# LED-RGB.net
KiCad netlist of a schematic drawn in EAGLE
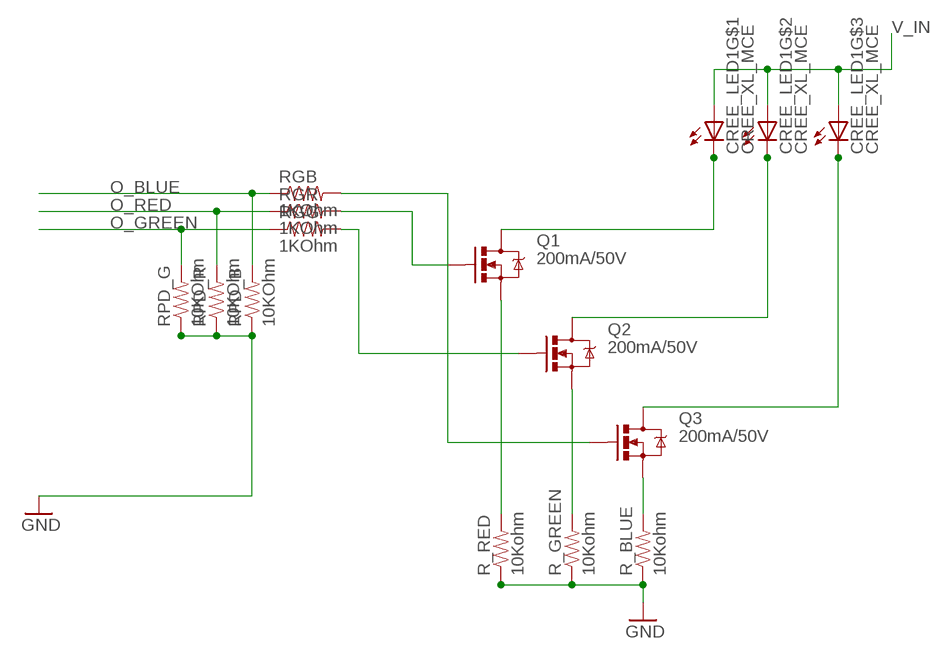
[diagram p0: schematic, sheet 1]

(export (version "E")
  (design (tool "Eeschema 10.0.6"))
  (components
    (comp (ref "CREE_LED1")
      (value "CREE_XL_MCE")
      (footprint "eagle-import:CREE_XL_MCE")
      (libsource (lib "eagle-import") (part "CREE_XL_MCE"))
    )
    (comp (ref "Q1")
      (value "200mA/50V")
      (footprint "eagle-import:SOT23-3")
      (libsource (lib "eagle-import") (part "MOSFET-NCHANNELBSS138"))
    )
    (comp (ref "Q2")
      (value "200mA/50V")
      (footprint "eagle-import:SOT23-3")
      (libsource (lib "eagle-import") (part "MOSFET-NCHANNELBSS138"))
    )
    (comp (ref "Q3")
      (value "200mA/50V")
      (footprint "eagle-import:SOT23-3")
      (libsource (lib "eagle-import") (part "MOSFET-NCHANNELBSS138"))
    )
    (comp (ref "RGB")
      (value "1KOhm")
      (footprint "eagle-import:0805")
      (libsource (lib "eagle-import") (part "RESISTOR0805-RES"))
    )
    (comp (ref "RGG")
      (value "1KOhm")
      (footprint "eagle-import:0805")
      (libsource (lib "eagle-import") (part "RESISTOR0805-RES"))
    )
    (comp (ref "RGR")
      (value "1KOhm")
      (footprint "eagle-import:0805")
      (libsource (lib "eagle-import") (part "RESISTOR0805-RES"))
    )
    (comp (ref "RPD_B")
      (value "10KOhm")
      (footprint "eagle-import:0805")
      (libsource (lib "eagle-import") (part "RESISTOR0805-RES"))
    )
    (comp (ref "RPD_G")
      (value "10KOhm")
      (footprint "eagle-import:0805")
      (libsource (lib "eagle-import") (part "RESISTOR0805-RES"))
    )
    (comp (ref "RPD_R")
      (value "10KOhm")
      (footprint "eagle-import:0805")
      (libsource (lib "eagle-import") (part "RESISTOR0805-RES"))
    )
    (comp (ref "R_BLUE")
      (value "10Kohm")
      (footprint "eagle-import:0805")
      (libsource (lib "eagle-import") (part "RESISTOR0805-RES"))
    )
    (comp (ref "R_GREEN")
      (value "10Kohm")
      (footprint "eagle-import:0805")
      (libsource (lib "eagle-import") (part "RESISTOR0805-RES"))
    )
    (comp (ref "R_RED")
      (value "10Kohm")
      (footprint "eagle-import:0805")
      (libsource (lib "eagle-import") (part "RESISTOR0805-RES"))
    )
  )
  (nets
    (net (code "1") (name "/O_BLUE") (class "Default")
      (node (ref "RGB") (pin "1") (pinfunction "1_1") (pintype "passive"))
      (node (ref "RPD_B") (pin "2") (pinfunction "2_2") (pintype "passive"))
    )
    (net (code "2") (name "/O_GREEN") (class "Default")
      (node (ref "RGG") (pin "1") (pinfunction "1_1") (pintype "passive"))
      (node (ref "RPD_G") (pin "2") (pinfunction "2_2") (pintype "passive"))
    )
    (net (code "3") (name "/O_RED") (class "Default")
      (node (ref "RGR") (pin "1") (pinfunction "1_1") (pintype "passive"))
      (node (ref "RPD_R") (pin "2") (pinfunction "2_2") (pintype "passive"))
    )
    (net (code "4") (name "/V_IN") (class "Default")
      (node (ref "CREE_LED1") (pin "1") (pinfunction "A_1") (pintype "passive"))
      (node (ref "CREE_LED1") (pin "2") (pinfunction "A_2") (pintype "passive"))
      (node (ref "CREE_LED1") (pin "3") (pinfunction "A_3") (pintype "passive"))
    )
    (net (code "5") (name "GND") (class "Default")
      (node (ref "RPD_B") (pin "1") (pinfunction "1_1") (pintype "passive"))
      (node (ref "RPD_G") (pin "1") (pinfunction "1_1") (pintype "passive"))
      (node (ref "RPD_R") (pin "1") (pinfunction "1_1") (pintype "passive"))
      (node (ref "R_BLUE") (pin "1") (pinfunction "1_1") (pintype "passive"))
      (node (ref "R_GREEN") (pin "1") (pinfunction "1_1") (pintype "passive"))
      (node (ref "R_RED") (pin "1") (pinfunction "1_1") (pintype "passive"))
    )
    (net (code "6") (name "Net-(CREE_LED1A-C)") (class "Default")
      (node (ref "CREE_LED1") (pin "8") (pinfunction "C_8") (pintype "passive"))
      (node (ref "Q1") (pin "3") (pinfunction "D_3") (pintype "passive"))
    )
    (net (code "7") (name "Net-(CREE_LED1B-C)") (class "Default")
      (node (ref "CREE_LED1") (pin "7") (pinfunction "C_7") (pintype "passive"))
      (node (ref "Q2") (pin "3") (pinfunction "D_3") (pintype "passive"))
    )
    (net (code "8") (name "Net-(CREE_LED1C-C)") (class "Default")
      (node (ref "CREE_LED1") (pin "6") (pinfunction "C_6") (pintype "passive"))
      (node (ref "Q3") (pin "3") (pinfunction "D_3") (pintype "passive"))
    )
    (net (code "9") (name "Net-(Q1-G)") (class "Default")
      (node (ref "Q1") (pin "1") (pinfunction "G_1") (pintype "passive"))
      (node (ref "RGR") (pin "2") (pinfunction "2_2") (pintype "passive"))
    )
    (net (code "10") (name "Net-(Q1-S)") (class "Default")
      (node (ref "Q1") (pin "2") (pinfunction "S_2") (pintype "passive"))
      (node (ref "R_RED") (pin "2") (pinfunction "2_2") (pintype "passive"))
    )
    (net (code "11") (name "Net-(Q2-G)") (class "Default")
      (node (ref "Q2") (pin "1") (pinfunction "G_1") (pintype "passive"))
      (node (ref "RGG") (pin "2") (pinfunction "2_2") (pintype "passive"))
    )
    (net (code "12") (name "Net-(Q2-S)") (class "Default")
      (node (ref "Q2") (pin "2") (pinfunction "S_2") (pintype "passive"))
      (node (ref "R_GREEN") (pin "2") (pinfunction "2_2") (pintype "passive"))
    )
    (net (code "13") (name "Net-(Q3-G)") (class "Default")
      (node (ref "Q3") (pin "1") (pinfunction "G_1") (pintype "passive"))
      (node (ref "RGB") (pin "2") (pinfunction "2_2") (pintype "passive"))
    )
    (net (code "14") (name "Net-(Q3-S)") (class "Default")
      (node (ref "Q3") (pin "2") (pinfunction "S_2") (pintype "passive"))
      (node (ref "R_BLUE") (pin "2") (pinfunction "2_2") (pintype "passive"))
    )
  )
)
